# cv_led2.net
KiCad netlist of a schematic drawn in EAGLE
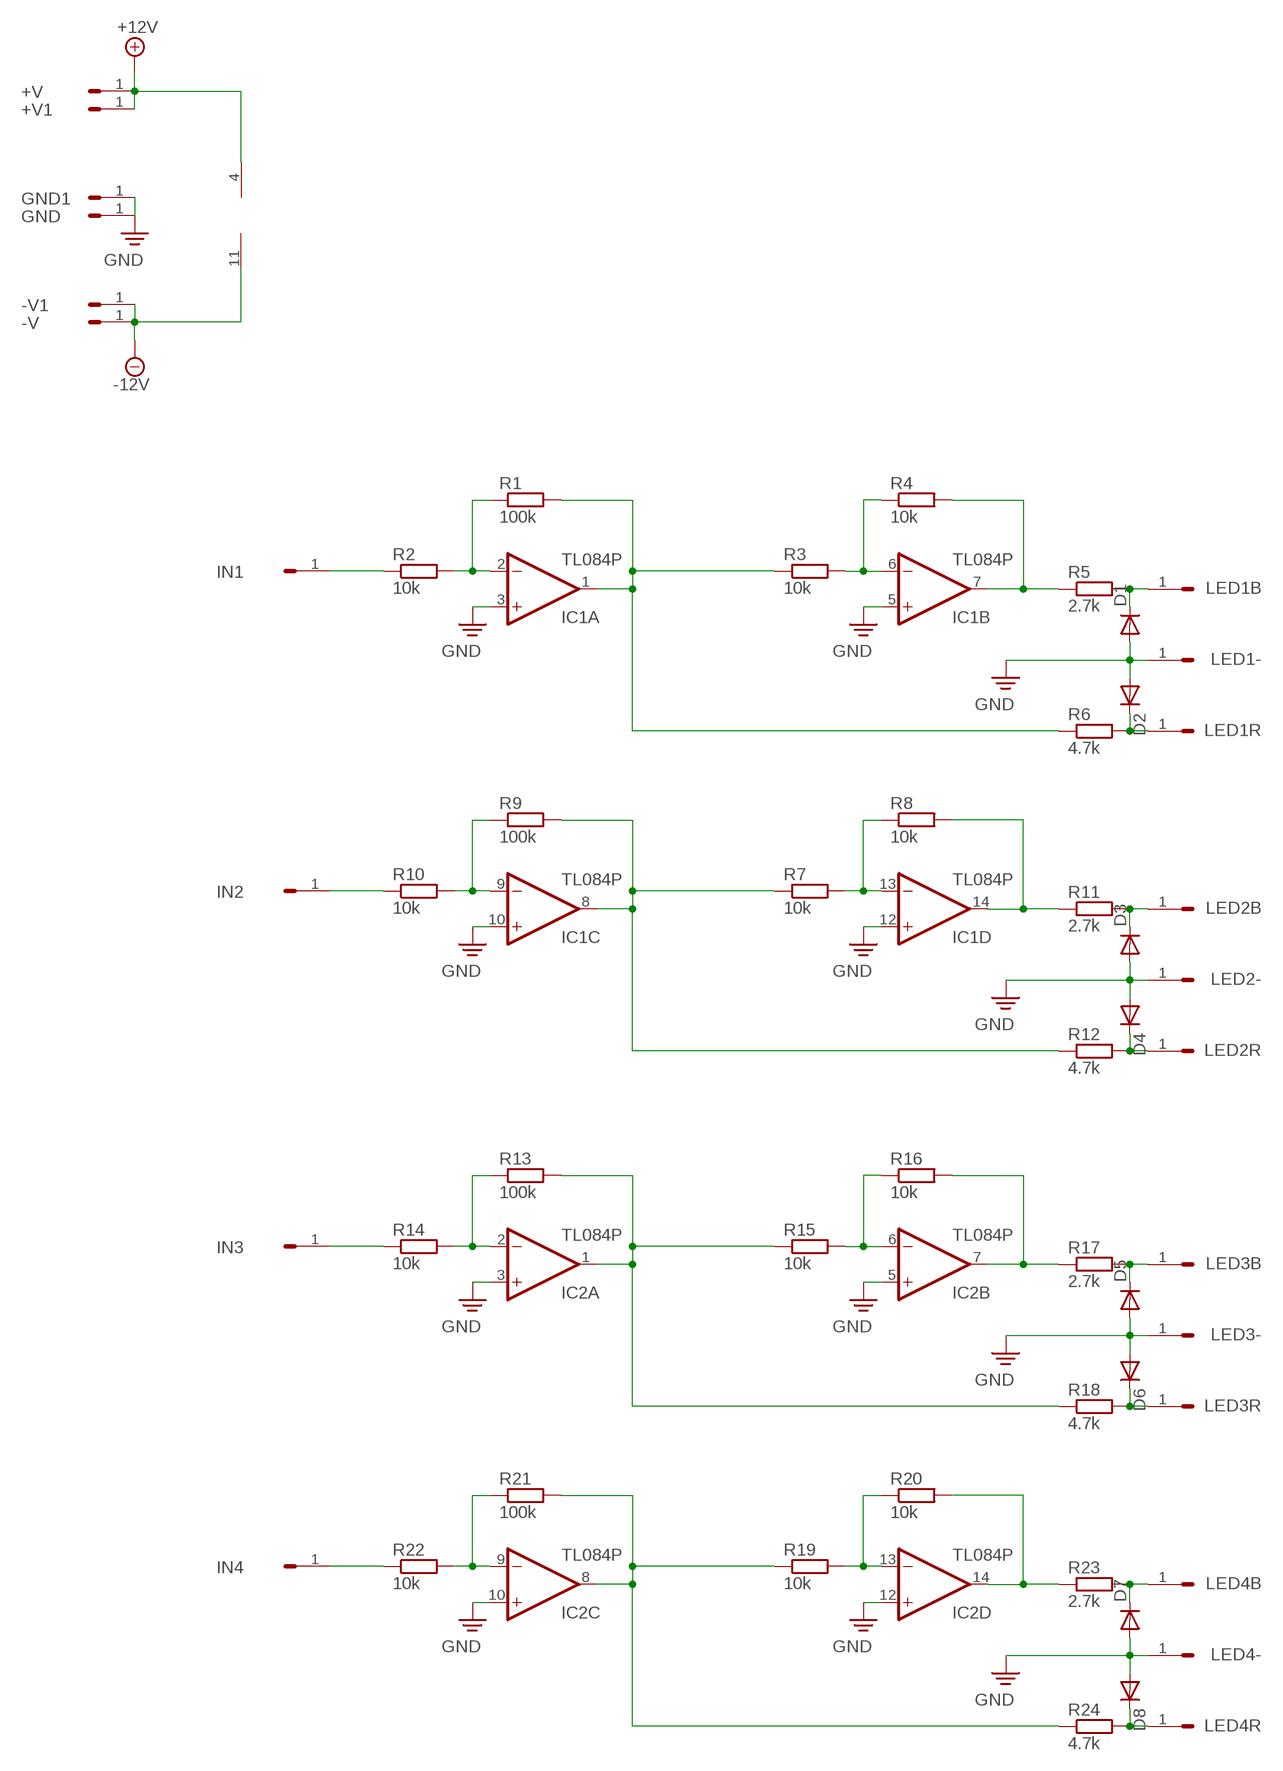
[diagram p0: schematic, sheet 1]

(export (version "E")
  (design (tool "Eeschema 10.0.6"))
  (components
    (comp (ref "+V")
      (value "HEADER/MALE/01")
      (footprint "eagle-import:HEADER_MALE_01")
      (fields (field (name "SPICEPREFIX") "X"))
      (libsource (lib "eagle-import") (part "HEADER/MALE/01"))
    )
    (comp (ref "+V1")
      (value "HEADER/MALE/01")
      (footprint "eagle-import:HEADER_MALE_01")
      (fields (field (name "SPICEPREFIX") "X"))
      (libsource (lib "eagle-import") (part "HEADER/MALE/01"))
    )
    (comp (ref "-V")
      (value "HEADER/MALE/01")
      (footprint "eagle-import:HEADER_MALE_01")
      (fields (field (name "SPICEPREFIX") "X"))
      (libsource (lib "eagle-import") (part "HEADER/MALE/01"))
    )
    (comp (ref "-V1")
      (value "HEADER/MALE/01")
      (footprint "eagle-import:HEADER_MALE_01")
      (fields (field (name "SPICEPREFIX") "X"))
      (libsource (lib "eagle-import") (part "HEADER/MALE/01"))
    )
    (comp (ref "D1")
      (value "1N4148DO35-7")
      (footprint "eagle-import:DO35-7")
      (libsource (lib "eagle-import") (part "1N4148DO35-7"))
    )
    (comp (ref "D2")
      (value "1N4148DO35-7")
      (footprint "eagle-import:DO35-7")
      (libsource (lib "eagle-import") (part "1N4148DO35-7"))
    )
    (comp (ref "D3")
      (value "1N4148DO35-7")
      (footprint "eagle-import:DO35-7")
      (libsource (lib "eagle-import") (part "1N4148DO35-7"))
    )
    (comp (ref "D4")
      (value "1N4148DO35-7")
      (footprint "eagle-import:DO35-7")
      (libsource (lib "eagle-import") (part "1N4148DO35-7"))
    )
    (comp (ref "D5")
      (value "1N4148DO35-7")
      (footprint "eagle-import:DO35-7")
      (libsource (lib "eagle-import") (part "1N4148DO35-7"))
    )
    (comp (ref "D6")
      (value "1N4148DO35-7")
      (footprint "eagle-import:DO35-7")
      (libsource (lib "eagle-import") (part "1N4148DO35-7"))
    )
    (comp (ref "D7")
      (value "1N4148DO35-7")
      (footprint "eagle-import:DO35-7")
      (libsource (lib "eagle-import") (part "1N4148DO35-7"))
    )
    (comp (ref "D8")
      (value "1N4148DO35-7")
      (footprint "eagle-import:DO35-7")
      (libsource (lib "eagle-import") (part "1N4148DO35-7"))
    )
    (comp (ref "GND")
      (value "HEADER/MALE/01")
      (footprint "eagle-import:HEADER_MALE_01")
      (fields (field (name "SPICEPREFIX") "X"))
      (libsource (lib "eagle-import") (part "HEADER/MALE/01"))
    )
    (comp (ref "GND1")
      (value "HEADER/MALE/01")
      (footprint "eagle-import:HEADER_MALE_01")
      (fields (field (name "SPICEPREFIX") "X"))
      (libsource (lib "eagle-import") (part "HEADER/MALE/01"))
    )
    (comp (ref "IC1")
      (value "TL084P")
      (footprint "eagle-import:DIL14")
      (libsource (lib "eagle-import") (part "TL084P"))
    )
    (comp (ref "IC2")
      (value "TL084P")
      (footprint "eagle-import:DIL14")
      (libsource (lib "eagle-import") (part "TL084P"))
    )
    (comp (ref "IN1")
      (value "HEADER/MALE/01")
      (footprint "eagle-import:HEADER_MALE_01")
      (fields (field (name "SPICEPREFIX") "X"))
      (libsource (lib "eagle-import") (part "HEADER/MALE/01"))
    )
    (comp (ref "IN2")
      (value "HEADER/MALE/01")
      (footprint "eagle-import:HEADER_MALE_01")
      (fields (field (name "SPICEPREFIX") "X"))
      (libsource (lib "eagle-import") (part "HEADER/MALE/01"))
    )
    (comp (ref "IN3")
      (value "HEADER/MALE/01")
      (footprint "eagle-import:HEADER_MALE_01")
      (fields (field (name "SPICEPREFIX") "X"))
      (libsource (lib "eagle-import") (part "HEADER/MALE/01"))
    )
    (comp (ref "IN4")
      (value "HEADER/MALE/01")
      (footprint "eagle-import:HEADER_MALE_01")
      (fields (field (name "SPICEPREFIX") "X"))
      (libsource (lib "eagle-import") (part "HEADER/MALE/01"))
    )
    (comp (ref "LED1-")
      (value "HEADER/MALE/01")
      (footprint "eagle-import:HEADER_MALE_01")
      (fields (field (name "SPICEPREFIX") "X"))
      (libsource (lib "eagle-import") (part "HEADER/MALE/01"))
    )
    (comp (ref "LED1B")
      (value "HEADER/MALE/01")
      (footprint "eagle-import:HEADER_MALE_01")
      (fields (field (name "SPICEPREFIX") "X"))
      (libsource (lib "eagle-import") (part "HEADER/MALE/01"))
    )
    (comp (ref "LED1R")
      (value "HEADER/MALE/01")
      (footprint "eagle-import:HEADER_MALE_01")
      (fields (field (name "SPICEPREFIX") "X"))
      (libsource (lib "eagle-import") (part "HEADER/MALE/01"))
    )
    (comp (ref "LED2-")
      (value "HEADER/MALE/01")
      (footprint "eagle-import:HEADER_MALE_01")
      (fields (field (name "SPICEPREFIX") "X"))
      (libsource (lib "eagle-import") (part "HEADER/MALE/01"))
    )
    (comp (ref "LED2B")
      (value "HEADER/MALE/01")
      (footprint "eagle-import:HEADER_MALE_01")
      (fields (field (name "SPICEPREFIX") "X"))
      (libsource (lib "eagle-import") (part "HEADER/MALE/01"))
    )
    (comp (ref "LED2R")
      (value "HEADER/MALE/01")
      (footprint "eagle-import:HEADER_MALE_01")
      (fields (field (name "SPICEPREFIX") "X"))
      (libsource (lib "eagle-import") (part "HEADER/MALE/01"))
    )
    (comp (ref "LED3-")
      (value "HEADER/MALE/01")
      (footprint "eagle-import:HEADER_MALE_01")
      (fields (field (name "SPICEPREFIX") "X"))
      (libsource (lib "eagle-import") (part "HEADER/MALE/01"))
    )
    (comp (ref "LED3B")
      (value "HEADER/MALE/01")
      (footprint "eagle-import:HEADER_MALE_01")
      (fields (field (name "SPICEPREFIX") "X"))
      (libsource (lib "eagle-import") (part "HEADER/MALE/01"))
    )
    (comp (ref "LED3R")
      (value "HEADER/MALE/01")
      (footprint "eagle-import:HEADER_MALE_01")
      (fields (field (name "SPICEPREFIX") "X"))
      (libsource (lib "eagle-import") (part "HEADER/MALE/01"))
    )
    (comp (ref "LED4-")
      (value "HEADER/MALE/01")
      (footprint "eagle-import:HEADER_MALE_01")
      (fields (field (name "SPICEPREFIX") "X"))
      (libsource (lib "eagle-import") (part "HEADER/MALE/01"))
    )
    (comp (ref "LED4B")
      (value "HEADER/MALE/01")
      (footprint "eagle-import:HEADER_MALE_01")
      (fields (field (name "SPICEPREFIX") "X"))
      (libsource (lib "eagle-import") (part "HEADER/MALE/01"))
    )
    (comp (ref "LED4R")
      (value "HEADER/MALE/01")
      (footprint "eagle-import:HEADER_MALE_01")
      (fields (field (name "SPICEPREFIX") "X"))
      (libsource (lib "eagle-import") (part "HEADER/MALE/01"))
    )
    (comp (ref "R1")
      (value "100k")
      (footprint "eagle-import:RESISTOR_7.5")
      (libsource (lib "eagle-import") (part "RESISTORRESISTOR/UPRIGHT/7.5"))
    )
    (comp (ref "R2")
      (value "10k")
      (footprint "eagle-import:RESISTOR_7.5")
      (libsource (lib "eagle-import") (part "RESISTORRESISTOR/UPRIGHT/7.5"))
    )
    (comp (ref "R3")
      (value "10k")
      (footprint "eagle-import:RESISTOR_7.5")
      (libsource (lib "eagle-import") (part "RESISTORRESISTOR/UPRIGHT/7.5"))
    )
    (comp (ref "R4")
      (value "10k")
      (footprint "eagle-import:RESISTOR_7.5")
      (libsource (lib "eagle-import") (part "RESISTORRESISTOR/UPRIGHT/7.5"))
    )
    (comp (ref "R5")
      (value "2.7k")
      (footprint "eagle-import:RESISTOR_7.5")
      (libsource (lib "eagle-import") (part "RESISTORRESISTOR/UPRIGHT/7.5"))
    )
    (comp (ref "R6")
      (value "4.7k")
      (footprint "eagle-import:RESISTOR_7.5")
      (libsource (lib "eagle-import") (part "RESISTORRESISTOR/UPRIGHT/7.5"))
    )
    (comp (ref "R7")
      (value "10k")
      (footprint "eagle-import:RESISTOR_7.5")
      (libsource (lib "eagle-import") (part "RESISTORRESISTOR/UPRIGHT/7.5"))
    )
    (comp (ref "R8")
      (value "10k")
      (footprint "eagle-import:RESISTOR_7.5")
      (libsource (lib "eagle-import") (part "RESISTORRESISTOR/UPRIGHT/7.5"))
    )
    (comp (ref "R9")
      (value "100k")
      (footprint "eagle-import:RESISTOR_7.5")
      (libsource (lib "eagle-import") (part "RESISTORRESISTOR/UPRIGHT/7.5"))
    )
    (comp (ref "R10")
      (value "10k")
      (footprint "eagle-import:RESISTOR_7.5")
      (libsource (lib "eagle-import") (part "RESISTORRESISTOR/UPRIGHT/7.5"))
    )
    (comp (ref "R11")
      (value "2.7k")
      (footprint "eagle-import:RESISTOR_7.5")
      (libsource (lib "eagle-import") (part "RESISTORRESISTOR/UPRIGHT/7.5"))
    )
    (comp (ref "R12")
      (value "4.7k")
      (footprint "eagle-import:RESISTOR_7.5")
      (libsource (lib "eagle-import") (part "RESISTORRESISTOR/UPRIGHT/7.5"))
    )
    (comp (ref "R13")
      (value "100k")
      (footprint "eagle-import:RESISTOR_7.5")
      (libsource (lib "eagle-import") (part "RESISTORRESISTOR/UPRIGHT/7.5"))
    )
    (comp (ref "R14")
      (value "10k")
      (footprint "eagle-import:RESISTOR_7.5")
      (libsource (lib "eagle-import") (part "RESISTORRESISTOR/UPRIGHT/7.5"))
    )
    (comp (ref "R15")
      (value "10k")
      (footprint "eagle-import:RESISTOR_7.5")
      (libsource (lib "eagle-import") (part "RESISTORRESISTOR/UPRIGHT/7.5"))
    )
    (comp (ref "R16")
      (value "10k")
      (footprint "eagle-import:RESISTOR_7.5")
      (libsource (lib "eagle-import") (part "RESISTORRESISTOR/UPRIGHT/7.5"))
    )
    (comp (ref "R17")
      (value "2.7k")
      (footprint "eagle-import:RESISTOR_7.5")
      (libsource (lib "eagle-import") (part "RESISTORRESISTOR/UPRIGHT/7.5"))
    )
    (comp (ref "R18")
      (value "4.7k")
      (footprint "eagle-import:RESISTOR_7.5")
      (libsource (lib "eagle-import") (part "RESISTORRESISTOR/UPRIGHT/7.5"))
    )
    (comp (ref "R19")
      (value "10k")
      (footprint "eagle-import:RESISTOR_7.5")
      (libsource (lib "eagle-import") (part "RESISTORRESISTOR/UPRIGHT/7.5"))
    )
    (comp (ref "R20")
      (value "10k")
      (footprint "eagle-import:RESISTOR_7.5")
      (libsource (lib "eagle-import") (part "RESISTORRESISTOR/UPRIGHT/7.5"))
    )
    (comp (ref "R21")
      (value "100k")
      (footprint "eagle-import:RESISTOR_7.5")
      (libsource (lib "eagle-import") (part "RESISTORRESISTOR/UPRIGHT/7.5"))
    )
    (comp (ref "R22")
      (value "10k")
      (footprint "eagle-import:RESISTOR_7.5")
      (libsource (lib "eagle-import") (part "RESISTORRESISTOR/UPRIGHT/7.5"))
    )
    (comp (ref "R23")
      (value "2.7k")
      (footprint "eagle-import:RESISTOR_7.5")
      (libsource (lib "eagle-import") (part "RESISTORRESISTOR/UPRIGHT/7.5"))
    )
    (comp (ref "R24")
      (value "4.7k")
      (footprint "eagle-import:RESISTOR_7.5")
      (libsource (lib "eagle-import") (part "RESISTORRESISTOR/UPRIGHT/7.5"))
    )
  )
  (nets
    (net (code "1") (name "+12V") (class "Default")
      (node (ref "+V") (pin "1") (pinfunction "3_1") (pintype "passive"))
      (node (ref "+V1") (pin "1") (pinfunction "3_1") (pintype "passive"))
      (node (ref "IC1") (pin "4") (pinfunction "V+_4") (pintype "power_in"))
    )
    (net (code "2") (name "-12V") (class "Default")
      (node (ref "-V") (pin "1") (pinfunction "3_1") (pintype "passive"))
      (node (ref "-V1") (pin "1") (pinfunction "3_1") (pintype "passive"))
      (node (ref "IC1") (pin "11") (pinfunction "V-_11") (pintype "power_in"))
    )
    (net (code "3") (name "GND") (class "Default")
      (node (ref "D1") (pin "A") (pinfunction "A_A") (pintype "passive"))
      (node (ref "D2") (pin "A") (pinfunction "A_A") (pintype "passive"))
      (node (ref "D3") (pin "A") (pinfunction "A_A") (pintype "passive"))
      (node (ref "D4") (pin "A") (pinfunction "A_A") (pintype "passive"))
      (node (ref "D5") (pin "A") (pinfunction "A_A") (pintype "passive"))
      (node (ref "D6") (pin "A") (pinfunction "A_A") (pintype "passive"))
      (node (ref "D7") (pin "A") (pinfunction "A_A") (pintype "passive"))
      (node (ref "D8") (pin "A") (pinfunction "A_A") (pintype "passive"))
      (node (ref "GND") (pin "1") (pinfunction "3_1") (pintype "passive"))
      (node (ref "GND1") (pin "1") (pinfunction "3_1") (pintype "passive"))
      (node (ref "IC1") (pin "10") (pinfunction "+IN_10") (pintype "input"))
      (node (ref "IC1") (pin "12") (pinfunction "+IN_12") (pintype "input"))
      (node (ref "IC1") (pin "3") (pinfunction "+IN_3") (pintype "input"))
      (node (ref "IC1") (pin "5") (pinfunction "+IN_5") (pintype "input"))
      (node (ref "IC2") (pin "10") (pinfunction "+IN_10") (pintype "input"))
      (node (ref "IC2") (pin "12") (pinfunction "+IN_12") (pintype "input"))
      (node (ref "IC2") (pin "3") (pinfunction "+IN_3") (pintype "input"))
      (node (ref "IC2") (pin "5") (pinfunction "+IN_5") (pintype "input"))
      (node (ref "LED1-") (pin "1") (pinfunction "3_1") (pintype "passive"))
      (node (ref "LED2-") (pin "1") (pinfunction "3_1") (pintype "passive"))
      (node (ref "LED3-") (pin "1") (pinfunction "3_1") (pintype "passive"))
      (node (ref "LED4-") (pin "1") (pinfunction "3_1") (pintype "passive"))
    )
    (net (code "4") (name "Net-(IC1A--IN)") (class "Default")
      (node (ref "IC1") (pin "2") (pinfunction "-IN_2") (pintype "input"))
      (node (ref "R1") (pin "1") (pinfunction "1_1") (pintype "passive"))
      (node (ref "R2") (pin "2") (pinfunction "2_2") (pintype "passive"))
    )
    (net (code "5") (name "Net-(IC1A-OUT)") (class "Default")
      (node (ref "IC1") (pin "1") (pinfunction "OUT_1") (pintype "output"))
      (node (ref "R1") (pin "2") (pinfunction "2_2") (pintype "passive"))
      (node (ref "R3") (pin "1") (pinfunction "1_1") (pintype "passive"))
      (node (ref "R6") (pin "1") (pinfunction "1_1") (pintype "passive"))
    )
    (net (code "6") (name "Net-(IC1B--IN)") (class "Default")
      (node (ref "IC1") (pin "6") (pinfunction "-IN_6") (pintype "input"))
      (node (ref "R3") (pin "2") (pinfunction "2_2") (pintype "passive"))
      (node (ref "R4") (pin "1") (pinfunction "1_1") (pintype "passive"))
    )
    (net (code "7") (name "Net-(IC1B-OUT)") (class "Default")
      (node (ref "IC1") (pin "7") (pinfunction "OUT_7") (pintype "output"))
      (node (ref "R4") (pin "2") (pinfunction "2_2") (pintype "passive"))
      (node (ref "R5") (pin "1") (pinfunction "1_1") (pintype "passive"))
    )
    (net (code "8") (name "Net-(IC1C--IN)") (class "Default")
      (node (ref "IC1") (pin "9") (pinfunction "-IN_9") (pintype "input"))
      (node (ref "R10") (pin "2") (pinfunction "2_2") (pintype "passive"))
      (node (ref "R9") (pin "1") (pinfunction "1_1") (pintype "passive"))
    )
    (net (code "9") (name "Net-(IC1C-OUT)") (class "Default")
      (node (ref "IC1") (pin "8") (pinfunction "OUT_8") (pintype "output"))
      (node (ref "R12") (pin "1") (pinfunction "1_1") (pintype "passive"))
      (node (ref "R7") (pin "1") (pinfunction "1_1") (pintype "passive"))
      (node (ref "R9") (pin "2") (pinfunction "2_2") (pintype "passive"))
    )
    (net (code "10") (name "Net-(IC1D--IN)") (class "Default")
      (node (ref "IC1") (pin "13") (pinfunction "-IN_13") (pintype "input"))
      (node (ref "R7") (pin "2") (pinfunction "2_2") (pintype "passive"))
      (node (ref "R8") (pin "1") (pinfunction "1_1") (pintype "passive"))
    )
    (net (code "11") (name "Net-(IC1D-OUT)") (class "Default")
      (node (ref "IC1") (pin "14") (pinfunction "OUT_14") (pintype "output"))
      (node (ref "R11") (pin "1") (pinfunction "1_1") (pintype "passive"))
      (node (ref "R8") (pin "2") (pinfunction "2_2") (pintype "passive"))
    )
    (net (code "12") (name "Net-(IC2A--IN)") (class "Default")
      (node (ref "IC2") (pin "2") (pinfunction "-IN_2") (pintype "input"))
      (node (ref "R13") (pin "1") (pinfunction "1_1") (pintype "passive"))
      (node (ref "R14") (pin "2") (pinfunction "2_2") (pintype "passive"))
    )
    (net (code "13") (name "Net-(IC2A-OUT)") (class "Default")
      (node (ref "IC2") (pin "1") (pinfunction "OUT_1") (pintype "output"))
      (node (ref "R13") (pin "2") (pinfunction "2_2") (pintype "passive"))
      (node (ref "R15") (pin "1") (pinfunction "1_1") (pintype "passive"))
      (node (ref "R18") (pin "1") (pinfunction "1_1") (pintype "passive"))
    )
    (net (code "14") (name "Net-(IC2B--IN)") (class "Default")
      (node (ref "IC2") (pin "6") (pinfunction "-IN_6") (pintype "input"))
      (node (ref "R15") (pin "2") (pinfunction "2_2") (pintype "passive"))
      (node (ref "R16") (pin "1") (pinfunction "1_1") (pintype "passive"))
    )
    (net (code "15") (name "Net-(IC2B-OUT)") (class "Default")
      (node (ref "IC2") (pin "7") (pinfunction "OUT_7") (pintype "output"))
      (node (ref "R16") (pin "2") (pinfunction "2_2") (pintype "passive"))
      (node (ref "R17") (pin "1") (pinfunction "1_1") (pintype "passive"))
    )
    (net (code "16") (name "Net-(IC2C--IN)") (class "Default")
      (node (ref "IC2") (pin "9") (pinfunction "-IN_9") (pintype "input"))
      (node (ref "R21") (pin "1") (pinfunction "1_1") (pintype "passive"))
      (node (ref "R22") (pin "2") (pinfunction "2_2") (pintype "passive"))
    )
    (net (code "17") (name "Net-(IC2C-OUT)") (class "Default")
      (node (ref "IC2") (pin "8") (pinfunction "OUT_8") (pintype "output"))
      (node (ref "R19") (pin "1") (pinfunction "1_1") (pintype "passive"))
      (node (ref "R21") (pin "2") (pinfunction "2_2") (pintype "passive"))
      (node (ref "R24") (pin "1") (pinfunction "1_1") (pintype "passive"))
    )
    (net (code "18") (name "Net-(IC2D--IN)") (class "Default")
      (node (ref "IC2") (pin "13") (pinfunction "-IN_13") (pintype "input"))
      (node (ref "R19") (pin "2") (pinfunction "2_2") (pintype "passive"))
      (node (ref "R20") (pin "1") (pinfunction "1_1") (pintype "passive"))
    )
    (net (code "19") (name "Net-(IC2D-OUT)") (class "Default")
      (node (ref "IC2") (pin "14") (pinfunction "OUT_14") (pintype "output"))
      (node (ref "R20") (pin "2") (pinfunction "2_2") (pintype "passive"))
      (node (ref "R23") (pin "1") (pinfunction "1_1") (pintype "passive"))
    )
    (net (code "20") (name "Net-(IN1-3)") (class "Default")
      (node (ref "IN1") (pin "1") (pinfunction "3_1") (pintype "passive"))
      (node (ref "R2") (pin "1") (pinfunction "1_1") (pintype "passive"))
    )
    (net (code "21") (name "Net-(IN2-3)") (class "Default")
      (node (ref "IN2") (pin "1") (pinfunction "3_1") (pintype "passive"))
      (node (ref "R10") (pin "1") (pinfunction "1_1") (pintype "passive"))
    )
    (net (code "22") (name "Net-(IN3-3)") (class "Default")
      (node (ref "IN3") (pin "1") (pinfunction "3_1") (pintype "passive"))
      (node (ref "R14") (pin "1") (pinfunction "1_1") (pintype "passive"))
    )
    (net (code "23") (name "Net-(IN4-3)") (class "Default")
      (node (ref "IN4") (pin "1") (pinfunction "3_1") (pintype "passive"))
      (node (ref "R22") (pin "1") (pinfunction "1_1") (pintype "passive"))
    )
    (net (code "24") (name "Net-(LED1B-3)") (class "Default")
      (node (ref "D1") (pin "C") (pinfunction "C_C") (pintype "passive"))
      (node (ref "LED1B") (pin "1") (pinfunction "3_1") (pintype "passive"))
      (node (ref "R5") (pin "2") (pinfunction "2_2") (pintype "passive"))
    )
    (net (code "25") (name "Net-(LED1R-3)") (class "Default")
      (node (ref "D2") (pin "C") (pinfunction "C_C") (pintype "passive"))
      (node (ref "LED1R") (pin "1") (pinfunction "3_1") (pintype "passive"))
      (node (ref "R6") (pin "2") (pinfunction "2_2") (pintype "passive"))
    )
    (net (code "26") (name "Net-(LED2B-3)") (class "Default")
      (node (ref "D3") (pin "C") (pinfunction "C_C") (pintype "passive"))
      (node (ref "LED2B") (pin "1") (pinfunction "3_1") (pintype "passive"))
      (node (ref "R11") (pin "2") (pinfunction "2_2") (pintype "passive"))
    )
    (net (code "27") (name "Net-(LED2R-3)") (class "Default")
      (node (ref "D4") (pin "C") (pinfunction "C_C") (pintype "passive"))
      (node (ref "LED2R") (pin "1") (pinfunction "3_1") (pintype "passive"))
      (node (ref "R12") (pin "2") (pinfunction "2_2") (pintype "passive"))
    )
    (net (code "28") (name "Net-(LED3B-3)") (class "Default")
      (node (ref "D5") (pin "C") (pinfunction "C_C") (pintype "passive"))
      (node (ref "LED3B") (pin "1") (pinfunction "3_1") (pintype "passive"))
      (node (ref "R17") (pin "2") (pinfunction "2_2") (pintype "passive"))
    )
    (net (code "29") (name "Net-(LED3R-3)") (class "Default")
      (node (ref "D6") (pin "C") (pinfunction "C_C") (pintype "passive"))
      (node (ref "LED3R") (pin "1") (pinfunction "3_1") (pintype "passive"))
      (node (ref "R18") (pin "2") (pinfunction "2_2") (pintype "passive"))
    )
    (net (code "30") (name "Net-(LED4B-3)") (class "Default")
      (node (ref "D7") (pin "C") (pinfunction "C_C") (pintype "passive"))
      (node (ref "LED4B") (pin "1") (pinfunction "3_1") (pintype "passive"))
      (node (ref "R23") (pin "2") (pinfunction "2_2") (pintype "passive"))
    )
    (net (code "31") (name "Net-(LED4R-3)") (class "Default")
      (node (ref "D8") (pin "C") (pinfunction "C_C") (pintype "passive"))
      (node (ref "LED4R") (pin "1") (pinfunction "3_1") (pintype "passive"))
      (node (ref "R24") (pin "2") (pinfunction "2_2") (pintype "passive"))
    )
  )
)
